# LEDtestBoard.net
KiCad netlist of a schematic drawn in EAGLE
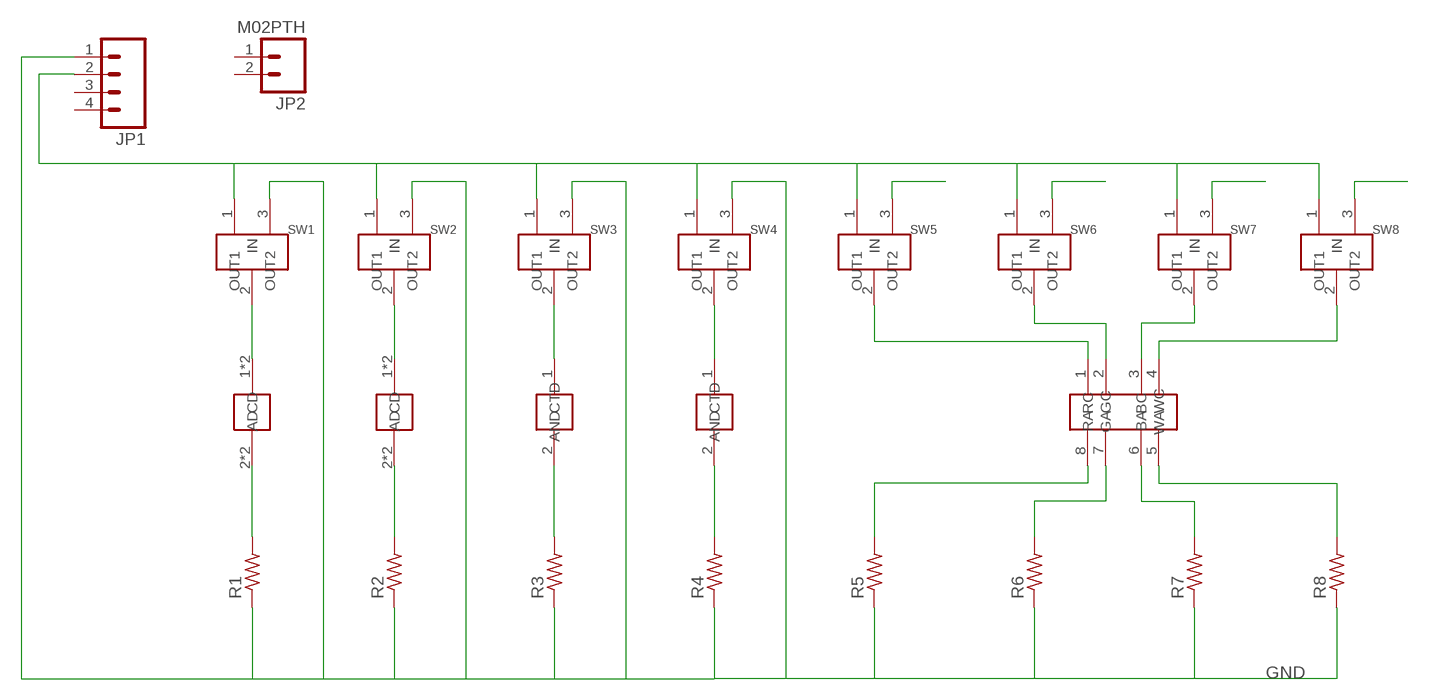
[diagram p0: schematic, sheet 1]

(export (version "E")
  (design (tool "Eeschema 10.0.6"))
  (components
    (comp (ref "D1")
      (value "SZA05A0A")
      (footprint "eagle-import:SZA05A0A")
      (libsource (lib "eagle-import") (part "SZA05A0A"))
    )
    (comp (ref "D2")
      (value "SZA05A0A")
      (footprint "eagle-import:SZA05A0A")
      (libsource (lib "eagle-import") (part "SZA05A0A"))
    )
    (comp (ref "D3")
      (value "XLAMP_COLOR")
      (footprint "eagle-import:8-SMD-LED")
      (libsource (lib "eagle-import") (part "XLAMP_COLOR"))
    )
    (comp (ref "D4")
      (value "LACN5MFBGB241Z")
      (footprint "eagle-import:2-SMD-LED-NO-EXP")
      (libsource (lib "eagle-import") (part "LACN5MFBGB241Z"))
    )
    (comp (ref "D5")
      (value "LACN5MFBGB241Z")
      (footprint "eagle-import:2-SMD-LED-NO-EXP")
      (libsource (lib "eagle-import") (part "LACN5MFBGB241Z"))
    )
    (comp (ref "JP1")
      (value "M04PTH")
      (footprint "eagle-import:1X04")
      (libsource (lib "eagle-import") (part "M04PTH"))
    )
    (comp (ref "JP2")
      (value "M02PTH")
      (footprint "eagle-import:1X02")
      (libsource (lib "eagle-import") (part "M02PTH"))
    )
    (comp (ref "R1")
      (value "R-US_R0603")
      (footprint "eagle-import:R0603")
      (libsource (lib "eagle-import") (part "R-US_R0603"))
    )
    (comp (ref "R2")
      (value "R-US_R0603")
      (footprint "eagle-import:R0603")
      (libsource (lib "eagle-import") (part "R-US_R0603"))
    )
    (comp (ref "R3")
      (value "R-US_R0603")
      (footprint "eagle-import:R0603")
      (libsource (lib "eagle-import") (part "R-US_R0603"))
    )
    (comp (ref "R4")
      (value "R-US_R0603")
      (footprint "eagle-import:R0603")
      (libsource (lib "eagle-import") (part "R-US_R0603"))
    )
    (comp (ref "R5")
      (value "R-US_R0603")
      (footprint "eagle-import:R0603")
      (libsource (lib "eagle-import") (part "R-US_R0603"))
    )
    (comp (ref "R6")
      (value "R-US_R0603")
      (footprint "eagle-import:R0603")
      (libsource (lib "eagle-import") (part "R-US_R0603"))
    )
    (comp (ref "R7")
      (value "R-US_R0603")
      (footprint "eagle-import:R0603")
      (libsource (lib "eagle-import") (part "R-US_R0603"))
    )
    (comp (ref "R8")
      (value "R-US_R0603")
      (footprint "eagle-import:R0603")
      (libsource (lib "eagle-import") (part "R-US_R0603"))
    )
    (comp (ref "SW1")
      (value "PCM12SMTR")
      (footprint "eagle-import:PCM12SMTR")
      (libsource (lib "eagle-import") (part "PCM12SMTR"))
    )
    (comp (ref "SW2")
      (value "PCM12SMTR")
      (footprint "eagle-import:PCM12SMTR")
      (libsource (lib "eagle-import") (part "PCM12SMTR"))
    )
    (comp (ref "SW3")
      (value "PCM12SMTR")
      (footprint "eagle-import:PCM12SMTR")
      (libsource (lib "eagle-import") (part "PCM12SMTR"))
    )
    (comp (ref "SW4")
      (value "PCM12SMTR")
      (footprint "eagle-import:PCM12SMTR")
      (libsource (lib "eagle-import") (part "PCM12SMTR"))
    )
    (comp (ref "SW5")
      (value "PCM12SMTR")
      (footprint "eagle-import:PCM12SMTR")
      (libsource (lib "eagle-import") (part "PCM12SMTR"))
    )
    (comp (ref "SW6")
      (value "PCM12SMTR")
      (footprint "eagle-import:PCM12SMTR")
      (libsource (lib "eagle-import") (part "PCM12SMTR"))
    )
    (comp (ref "SW7")
      (value "PCM12SMTR")
      (footprint "eagle-import:PCM12SMTR")
      (libsource (lib "eagle-import") (part "PCM12SMTR"))
    )
    (comp (ref "SW8")
      (value "PCM12SMTR")
      (footprint "eagle-import:PCM12SMTR")
      (libsource (lib "eagle-import") (part "PCM12SMTR"))
    )
  )
  (nets
    (net (code "1") (name "/GND") (class "Default")
      (node (ref "JP1") (pin "1") (pinfunction "1_1") (pintype "passive"))
      (node (ref "R1") (pin "1") (pinfunction "1_1") (pintype "passive"))
      (node (ref "R2") (pin "1") (pinfunction "1_1") (pintype "passive"))
      (node (ref "R3") (pin "1") (pinfunction "1_1") (pintype "passive"))
      (node (ref "R4") (pin "1") (pinfunction "1_1") (pintype "passive"))
      (node (ref "R5") (pin "1") (pinfunction "1_1") (pintype "passive"))
      (node (ref "R6") (pin "1") (pinfunction "1_1") (pintype "passive"))
      (node (ref "R7") (pin "1") (pinfunction "1_1") (pintype "passive"))
      (node (ref "R8") (pin "1") (pinfunction "1_1") (pintype "passive"))
      (node (ref "SW1") (pin "3") (pinfunction "OUT2_3") (pintype "bidirectional"))
      (node (ref "SW2") (pin "3") (pinfunction "OUT2_3") (pintype "bidirectional"))
      (node (ref "SW3") (pin "3") (pinfunction "OUT2_3") (pintype "bidirectional"))
      (node (ref "SW4") (pin "3") (pinfunction "OUT2_3") (pintype "bidirectional"))
      (node (ref "SW5") (pin "3") (pinfunction "OUT2_3") (pintype "bidirectional"))
      (node (ref "SW6") (pin "3") (pinfunction "OUT2_3") (pintype "bidirectional"))
      (node (ref "SW7") (pin "3") (pinfunction "OUT2_3") (pintype "bidirectional"))
      (node (ref "SW8") (pin "3") (pinfunction "OUT2_3") (pintype "bidirectional"))
    )
    (net (code "2") (name "Net-(D1-CD-Pad12)") (class "Default")
      (node (ref "D1") (pin "12") (pinfunction "CD_12") (pintype "bidirectional"))
      (node (ref "D1") (pin "2") (pinfunction "CD_2") (pintype "bidirectional"))
      (node (ref "R1") (pin "2") (pinfunction "2_2") (pintype "passive"))
    )
    (net (code "3") (name "Net-(D2-CD-Pad12)") (class "Default")
      (node (ref "D2") (pin "12") (pinfunction "CD_12") (pintype "bidirectional"))
      (node (ref "D2") (pin "2") (pinfunction "CD_2") (pintype "bidirectional"))
      (node (ref "R2") (pin "2") (pinfunction "2_2") (pintype "passive"))
    )
    (net (code "4") (name "Net-(D3-BA)") (class "Default")
      (node (ref "D3") (pin "3") (pinfunction "BA_3") (pintype "bidirectional"))
      (node (ref "SW7") (pin "2") (pinfunction "IN_2") (pintype "bidirectional"))
    )
    (net (code "5") (name "Net-(D3-BC)") (class "Default")
      (node (ref "D3") (pin "6") (pinfunction "BC_6") (pintype "bidirectional"))
      (node (ref "R7") (pin "2") (pinfunction "2_2") (pintype "passive"))
    )
    (net (code "6") (name "Net-(D3-GA)") (class "Default")
      (node (ref "D3") (pin "2") (pinfunction "GA_2") (pintype "bidirectional"))
      (node (ref "SW6") (pin "2") (pinfunction "IN_2") (pintype "bidirectional"))
    )
    (net (code "7") (name "Net-(D3-GC)") (class "Default")
      (node (ref "D3") (pin "7") (pinfunction "GC_7") (pintype "bidirectional"))
      (node (ref "R6") (pin "2") (pinfunction "2_2") (pintype "passive"))
    )
    (net (code "8") (name "Net-(D3-RA)") (class "Default")
      (node (ref "D3") (pin "1") (pinfunction "RA_1") (pintype "bidirectional"))
      (node (ref "SW5") (pin "2") (pinfunction "IN_2") (pintype "bidirectional"))
    )
    (net (code "9") (name "Net-(D3-RC)") (class "Default")
      (node (ref "D3") (pin "8") (pinfunction "RC_8") (pintype "bidirectional"))
      (node (ref "R5") (pin "2") (pinfunction "2_2") (pintype "passive"))
    )
    (net (code "10") (name "Net-(D3-WA)") (class "Default")
      (node (ref "D3") (pin "4") (pinfunction "WA_4") (pintype "bidirectional"))
      (node (ref "SW8") (pin "2") (pinfunction "IN_2") (pintype "bidirectional"))
    )
    (net (code "11") (name "Net-(D3-WC)") (class "Default")
      (node (ref "D3") (pin "5") (pinfunction "WC_5") (pintype "bidirectional"))
      (node (ref "R8") (pin "2") (pinfunction "2_2") (pintype "passive"))
    )
    (net (code "12") (name "Net-(D4-AND)") (class "Default")
      (node (ref "D4") (pin "1") (pinfunction "AND_1") (pintype "bidirectional"))
      (node (ref "SW3") (pin "2") (pinfunction "IN_2") (pintype "bidirectional"))
    )
    (net (code "13") (name "Net-(D4-CTD)") (class "Default")
      (node (ref "D4") (pin "2") (pinfunction "CTD_2") (pintype "bidirectional"))
      (node (ref "R3") (pin "2") (pinfunction "2_2") (pintype "passive"))
    )
    (net (code "14") (name "Net-(D5-AND)") (class "Default")
      (node (ref "D5") (pin "1") (pinfunction "AND_1") (pintype "bidirectional"))
      (node (ref "SW4") (pin "2") (pinfunction "IN_2") (pintype "bidirectional"))
    )
    (net (code "15") (name "Net-(D5-CTD)") (class "Default")
      (node (ref "D5") (pin "2") (pinfunction "CTD_2") (pintype "bidirectional"))
      (node (ref "R4") (pin "2") (pinfunction "2_2") (pintype "passive"))
    )
    (net (code "16") (name "Net-(SW1-IN)") (class "Default")
      (node (ref "D1") (pin "1") (pinfunction "AD_1") (pintype "bidirectional"))
      (node (ref "D1") (pin "11") (pinfunction "AD_11") (pintype "bidirectional"))
      (node (ref "SW1") (pin "2") (pinfunction "IN_2") (pintype "bidirectional"))
    )
    (net (code "17") (name "Net-(SW1-OUT1)") (class "Default")
      (node (ref "JP1") (pin "2") (pinfunction "2_2") (pintype "passive"))
      (node (ref "SW1") (pin "1") (pinfunction "OUT1_1") (pintype "bidirectional"))
      (node (ref "SW2") (pin "1") (pinfunction "OUT1_1") (pintype "bidirectional"))
      (node (ref "SW3") (pin "1") (pinfunction "OUT1_1") (pintype "bidirectional"))
      (node (ref "SW4") (pin "1") (pinfunction "OUT1_1") (pintype "bidirectional"))
      (node (ref "SW5") (pin "1") (pinfunction "OUT1_1") (pintype "bidirectional"))
      (node (ref "SW6") (pin "1") (pinfunction "OUT1_1") (pintype "bidirectional"))
      (node (ref "SW7") (pin "1") (pinfunction "OUT1_1") (pintype "bidirectional"))
      (node (ref "SW8") (pin "1") (pinfunction "OUT1_1") (pintype "bidirectional"))
    )
    (net (code "18") (name "Net-(SW2-IN)") (class "Default")
      (node (ref "D2") (pin "1") (pinfunction "AD_1") (pintype "bidirectional"))
      (node (ref "D2") (pin "11") (pinfunction "AD_11") (pintype "bidirectional"))
      (node (ref "SW2") (pin "2") (pinfunction "IN_2") (pintype "bidirectional"))
    )
    (net (code "19") (name "unconnected-(JP1-Pad3)") (class "Default")
      (node (ref "JP1") (pin "3") (pinfunction "3_3") (pintype "passive"))
    )
    (net (code "20") (name "unconnected-(JP1-Pad4)") (class "Default")
      (node (ref "JP1") (pin "4") (pinfunction "4_4") (pintype "passive"))
    )
    (net (code "21") (name "unconnected-(JP2-Pad1)") (class "Default")
      (node (ref "JP2") (pin "1") (pinfunction "1_1") (pintype "passive"))
    )
    (net (code "22") (name "unconnected-(JP2-Pad2)") (class "Default")
      (node (ref "JP2") (pin "2") (pinfunction "2_2") (pintype "passive"))
    )
  )
)
